# RS485_channel.net
KiCad netlist of a schematic drawn in Altium Designer
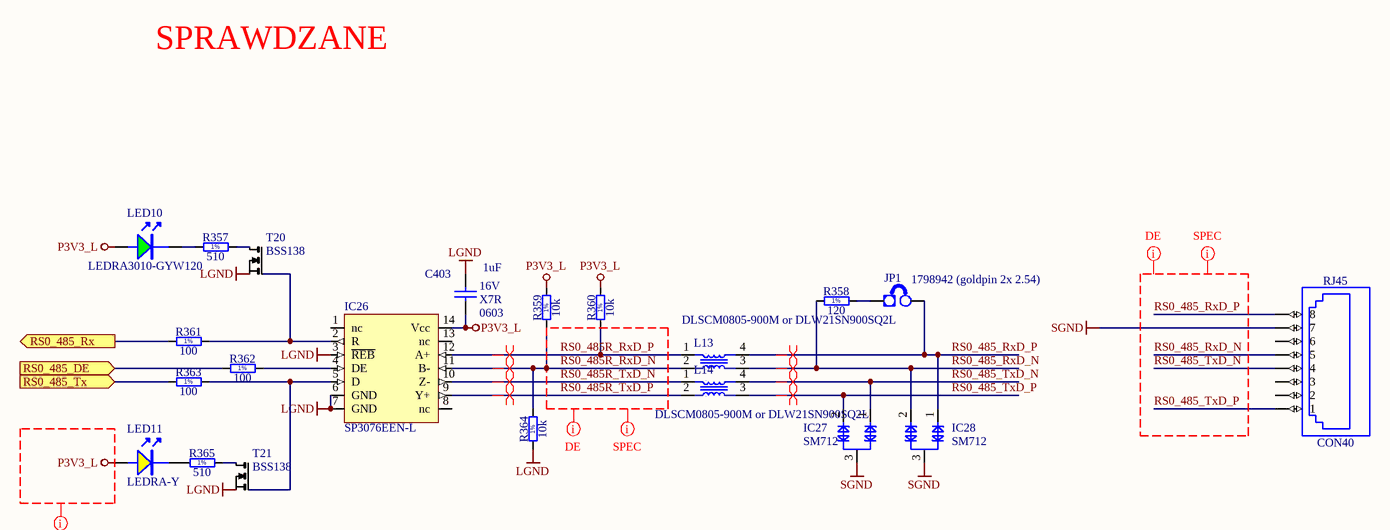
[diagram p0: RS485 channel.SchDoc]

(export (version "E")
  (design (tool "Eeschema 10.0.6"))
  (components
    (comp (ref "C403")
      (value "1uF")
      (footprint "CAPC1608X87N")
      (description "Non-polarised capacitor")
      (fields
        (field (name "PART NUMBER") "CC0603_1UF_16V_10%_X7R")
        (field (name "VOLTAGE") "16V")
        (field (name "TC") "X7R")
        (field (name "TOLERANCE") "±10%")
        (field (name "CASE") "0603")
        (field (name "AUTHOR") "CERN DEM JLC")
      )
      (libsource (lib "Capacitors") (part "Capacitor - non polarized"))
    )
    (comp (ref "CON40")
      (value "RJ45")
      (footprint "FCI_54602-908LF")
      (description "1 Port, 8 Positions, CAT3 RJ45 Horizontal Modular Jack")
      (fields
        (field (name "PART NUMBER") "FCI_54602-908LF")
        (field (name "MANUFACTURER") "FCI")
        (field (name "AUTHOR") "CERN DEM JLC")
      )
      (libsource (lib "Connectors") (part "FCI_54602-908LF"))
    )
    (comp (ref "IC26")
      (value "SP3076EEN-L")
      (footprint "SO-14")
      (description "3.3V, 1/8 Load, Failsafe  RS-485/RS422 Transceivers")
      (libsource (lib "LIBRARY_SCH") (part "DRV_SP3070/73/76"))
    )
    (comp (ref "IC27")
      (value "SM712")
      (footprint "SOT-23")
      (description "Asymmetrical TVS Diode for RS485")
      (libsource (lib "LIBRARY_SCH") (part "D_TVS_SM712"))
    )
    (comp (ref "IC28")
      (value "SM712")
      (footprint "SOT-23")
      (description "Asymmetrical TVS Diode for RS485")
      (libsource (lib "LIBRARY_SCH") (part "D_TVS_SM712"))
    )
    (comp (ref "JP1")
      (value "1798942 (goldpin 2x 2.54)")
      (footprint "jump")
      (description "Jumper")
      (libsource (lib "LIBRARY_SCH") (part "JUMPER"))
    )
    (comp (ref "L13")
      (value "DLSCM0805-900M or DLW21SN900SQ2L")
      (footprint "DLSCM0805")
      (description "Common Mode Choke 90R")
      (libsource (lib "LIBRARY_SCH") (part "L_CMC_DLSCM0805_90R"))
    )
    (comp (ref "L14")
      (value "DLSCM0805-900M or DLW21SN900SQ2L")
      (footprint "DLSCM0805")
      (description "Common Mode Choke 90R")
      (libsource (lib "LIBRARY_SCH") (part "L_CMC_DLSCM0805_90R"))
    )
    (comp (ref "LED10")
      (value "LEDRA3010-GYW120")
      (footprint "LED_KPA3010_G")
      (description "LED (Maritex)")
      (libsource (lib "LIBRARY_SCH") (part "LED_SMD_90deg_G"))
    )
    (comp (ref "LED11")
      (value "LEDRA-Y")
      (footprint "LED_KPA3010_Y")
      (description "LED (maritex)")
      (libsource (lib "LIBRARY_SCH") (part "LED_SMD_90deg_Y"))
    )
    (comp (ref "R357")
      (value "510")
      (footprint "RESC1608X55N")
      (description "Resistor - 1%")
      (fields
        (field (name "PART NUMBER") "R0603_510R_1%_0.1W_100PPM")
        (field (name "POWER") "0.1W")
        (field (name "AUTHOR") "CERN DEM JLC")
      )
      (libsource (lib "Resistors") (part "Resistor - 1%"))
    )
    (comp (ref "R358")
      (value "120")
      (footprint "RESC3216X65N")
      (description "Resistor - 1%")
      (fields
        (field (name "PART NUMBER") "R1206_120R_1%_0.25W_100PPM")
        (field (name "POWER") "0.25W")
        (field (name "AUTHOR") "CERN DEM JLC")
      )
      (libsource (lib "Resistors") (part "Resistor - 1%"))
    )
    (comp (ref "R359")
      (value "10k")
      (footprint "RESC1005X40N")
      (description "Resistor - 1%")
      (fields
        (field (name "PART NUMBER") "R0402_10K_1%_0.0625W_100PPM")
        (field (name "POWER") "0.0625W")
        (field (name "AUTHOR") "CERN DEM JLC")
      )
      (libsource (lib "Resistors") (part "Resistor - 1%"))
    )
    (comp (ref "R360")
      (value "10k")
      (footprint "RESC1005X40N")
      (description "Resistor - 1%")
      (fields
        (field (name "PART NUMBER") "R0402_10K_1%_0.0625W_100PPM")
        (field (name "POWER") "0.0625W")
        (field (name "AUTHOR") "CERN DEM JLC")
      )
      (libsource (lib "Resistors") (part "Resistor - 1%"))
    )
    (comp (ref "R361")
      (value "100")
      (footprint "RESC1005X40N")
      (description "Resistor - 1%")
      (fields
        (field (name "PART NUMBER") "R0402_100R_1%_0.0625W_100PPM")
        (field (name "POWER") "0.0625W")
        (field (name "AUTHOR") "CERN DEM JLC")
      )
      (libsource (lib "Resistors") (part "Resistor - 1%"))
    )
    (comp (ref "R362")
      (value "100")
      (footprint "RESC1005X40N")
      (description "Resistor - 1%")
      (fields
        (field (name "PART NUMBER") "R0402_100R_1%_0.0625W_100PPM")
        (field (name "POWER") "0.0625W")
        (field (name "AUTHOR") "CERN DEM JLC")
      )
      (libsource (lib "Resistors") (part "Resistor - 1%"))
    )
    (comp (ref "R363")
      (value "100")
      (footprint "RESC1005X40N")
      (description "Resistor - 1%")
      (fields
        (field (name "PART NUMBER") "R0402_100R_1%_0.0625W_100PPM")
        (field (name "POWER") "0.0625W")
        (field (name "AUTHOR") "CERN DEM JLC")
      )
      (libsource (lib "Resistors") (part "Resistor - 1%"))
    )
    (comp (ref "R364")
      (value "10k")
      (footprint "RESC1005X40N")
      (description "Resistor - 1%")
      (fields
        (field (name "PART NUMBER") "R0402_10K_1%_0.0625W_100PPM")
        (field (name "POWER") "0.0625W")
        (field (name "AUTHOR") "CERN DEM JLC")
      )
      (libsource (lib "Resistors") (part "Resistor - 1%"))
    )
    (comp (ref "R365")
      (value "510")
      (footprint "RESC1608X55N")
      (description "Resistor - 1%")
      (fields
        (field (name "PART NUMBER") "R0603_510R_1%_0.1W_100PPM")
        (field (name "POWER") "0.1W")
        (field (name "AUTHOR") "CERN DEM JLC")
      )
      (libsource (lib "Resistors") (part "Resistor - 1%"))
    )
    (comp (ref "T20") (value "BSS138") (footprint "SOT-23") (libsource (lib "LIBRARY_SCH") (part "Q_BSS138")))
    (comp (ref "T21") (value "BSS138") (footprint "SOT-23") (libsource (lib "LIBRARY_SCH") (part "Q_BSS138")))
  )
  (nets
    (net (code "1") (name "/RS0_485R_RxD_N") (class "Default")
      (node (ref "IC26") (pin "11") (pinfunction "B-_11") (pintype "input"))
      (node (ref "L13") (pin "2") (pinfunction "2_2") (pintype "passive"))
      (node (ref "R359") (pin "1") (pinfunction "1_1") (pintype "passive"))
      (node (ref "R364") (pin "2") (pinfunction "2_2") (pintype "passive"))
    )
    (net (code "2") (name "/RS0_485R_RxD_P") (class "Default")
      (node (ref "IC26") (pin "12") (pinfunction "A+_12") (pintype "input"))
      (node (ref "L13") (pin "1") (pinfunction "1_1") (pintype "passive"))
      (node (ref "R360") (pin "1") (pinfunction "1_1") (pintype "passive"))
    )
    (net (code "3") (name "/RS0_485R_TxD_N") (class "Default")
      (node (ref "IC26") (pin "10") (pinfunction "Z-_10") (pintype "output"))
      (node (ref "L14") (pin "1") (pinfunction "1_1") (pintype "passive"))
    )
    (net (code "4") (name "/RS0_485R_TxD_P") (class "Default")
      (node (ref "IC26") (pin "9") (pinfunction "Y+_9") (pintype "output"))
      (node (ref "L14") (pin "2") (pinfunction "2_2") (pintype "passive"))
    )
    (net (code "5") (name "/RS0_485_DE") (class "Default")
      (node (ref "R362") (pin "1") (pinfunction "1_1") (pintype "passive"))
    )
    (net (code "6") (name "/RS0_485_Rx") (class "Default")
      (node (ref "R361") (pin "1") (pinfunction "1_1") (pintype "passive"))
    )
    (net (code "7") (name "/RS0_485_RxD_N") (class "Default")
      (node (ref "CON40") (pin "5") (pinfunction "5_5") (pintype "bidirectional"))
      (node (ref "IC28") (pin "2") (pinfunction "2_2") (pintype "passive"))
      (node (ref "L13") (pin "3") (pinfunction "3_3") (pintype "passive"))
      (node (ref "R358") (pin "1") (pinfunction "1_1") (pintype "passive"))
    )
    (net (code "8") (name "/RS0_485_RxD_P") (class "Default")
      (node (ref "CON40") (pin "8") (pinfunction "8_8") (pintype "bidirectional"))
      (node (ref "IC28") (pin "1") (pinfunction "1_1") (pintype "passive"))
      (node (ref "JP1") (pin "2") (pinfunction "E2_2") (pintype "passive"))
      (node (ref "L13") (pin "4") (pinfunction "4_4") (pintype "passive"))
    )
    (net (code "9") (name "/RS0_485_Tx") (class "Default")
      (node (ref "R363") (pin "1") (pinfunction "1_1") (pintype "passive"))
    )
    (net (code "10") (name "/RS0_485_TxD_N") (class "Default")
      (node (ref "CON40") (pin "4") (pinfunction "4_4") (pintype "bidirectional"))
      (node (ref "IC27") (pin "1") (pinfunction "1_1") (pintype "passive"))
      (node (ref "L14") (pin "4") (pinfunction "4_4") (pintype "passive"))
    )
    (net (code "11") (name "/RS0_485_TxD_P") (class "Default")
      (node (ref "CON40") (pin "1") (pinfunction "1_1") (pintype "bidirectional"))
      (node (ref "IC27") (pin "2") (pinfunction "2_2") (pintype "passive"))
      (node (ref "L14") (pin "3") (pinfunction "3_3") (pintype "passive"))
    )
    (net (code "12") (name "LGND") (class "Default")
      (node (ref "C403") (pin "2") (pinfunction "2_2") (pintype "passive"))
      (node (ref "IC26") (pin "3") (pinfunction "~{REB}_3") (pintype "input"))
      (node (ref "IC26") (pin "6") (pinfunction "GND_6") (pintype "power_in"))
      (node (ref "IC26") (pin "7") (pinfunction "GND_7") (pintype "power_in"))
      (node (ref "R364") (pin "1") (pinfunction "1_1") (pintype "passive"))
      (node (ref "T20") (pin "2") (pinfunction "S_2") (pintype "passive"))
      (node (ref "T21") (pin "2") (pinfunction "S_2") (pintype "passive"))
    )
    (net (code "13") (name "Net-(IC26-D)") (class "Default")
      (node (ref "IC26") (pin "5") (pinfunction "D_5") (pintype "input"))
      (node (ref "R363") (pin "2") (pinfunction "2_2") (pintype "passive"))
      (node (ref "T21") (pin "1") (pinfunction "G_1") (pintype "input"))
    )
    (net (code "14") (name "Net-(IC26-DE)") (class "Default")
      (node (ref "IC26") (pin "4") (pinfunction "DE_4") (pintype "input"))
      (node (ref "R362") (pin "2") (pinfunction "2_2") (pintype "passive"))
    )
    (net (code "15") (name "Net-(IC26-R)") (class "Default")
      (node (ref "IC26") (pin "2") (pinfunction "R_2") (pintype "output"))
      (node (ref "R361") (pin "2") (pinfunction "2_2") (pintype "passive"))
      (node (ref "T20") (pin "1") (pinfunction "G_1") (pintype "input"))
    )
    (net (code "16") (name "Net-(JP1-E1)") (class "Default")
      (node (ref "JP1") (pin "1") (pinfunction "E1_1") (pintype "passive"))
      (node (ref "R358") (pin "2") (pinfunction "2_2") (pintype "passive"))
    )
    (net (code "17") (name "Net-(LED10-PadK)") (class "Default")
      (node (ref "LED10") (pin "K") (pinfunction "K_K") (pintype "passive"))
      (node (ref "R357") (pin "1") (pinfunction "1_1") (pintype "passive"))
    )
    (net (code "18") (name "Net-(LED11-PadK)") (class "Default")
      (node (ref "LED11") (pin "K") (pinfunction "K_K") (pintype "passive"))
      (node (ref "R365") (pin "1") (pinfunction "1_1") (pintype "passive"))
    )
    (net (code "19") (name "Net-(T20-D)") (class "Default")
      (node (ref "R357") (pin "2") (pinfunction "2_2") (pintype "passive"))
      (node (ref "T20") (pin "3") (pinfunction "D_3") (pintype "passive"))
    )
    (net (code "20") (name "Net-(T21-D)") (class "Default")
      (node (ref "R365") (pin "2") (pinfunction "2_2") (pintype "passive"))
      (node (ref "T21") (pin "3") (pinfunction "D_3") (pintype "passive"))
    )
    (net (code "21") (name "P3V3_L") (class "Default")
      (node (ref "C403") (pin "1") (pinfunction "1_1") (pintype "passive"))
      (node (ref "IC26") (pin "14") (pinfunction "Vcc_14") (pintype "power_in"))
      (node (ref "LED10") (pin "A") (pinfunction "A_A") (pintype "passive"))
      (node (ref "LED11") (pin "A") (pinfunction "A_A") (pintype "passive"))
      (node (ref "R359") (pin "2") (pinfunction "2_2") (pintype "passive"))
      (node (ref "R360") (pin "2") (pinfunction "2_2") (pintype "passive"))
    )
    (net (code "22") (name "SGND") (class "Default")
      (node (ref "CON40") (pin "7") (pinfunction "7_7") (pintype "bidirectional"))
      (node (ref "IC27") (pin "3") (pinfunction "3_3") (pintype "passive"))
      (node (ref "IC28") (pin "3") (pinfunction "3_3") (pintype "passive"))
    )
    (net (code "23") (name "unconnected-(CON40-Pad2)") (class "Default")
      (node (ref "CON40") (pin "2") (pinfunction "2_2") (pintype "bidirectional"))
    )
    (net (code "24") (name "unconnected-(CON40-Pad3)") (class "Default")
      (node (ref "CON40") (pin "3") (pinfunction "3_3") (pintype "bidirectional"))
    )
    (net (code "25") (name "unconnected-(CON40-Pad6)") (class "Default")
      (node (ref "CON40") (pin "6") (pinfunction "6_6") (pintype "bidirectional"))
    )
    (net (code "26") (name "unconnected-(IC26-nc-Pad1)") (class "Default")
      (node (ref "IC26") (pin "1") (pinfunction "nc_1") (pintype "passive"))
    )
    (net (code "27") (name "unconnected-(IC26-nc-Pad8)") (class "Default")
      (node (ref "IC26") (pin "8") (pinfunction "nc_8") (pintype "passive"))
    )
    (net (code "28") (name "unconnected-(IC26-nc-Pad13)") (class "Default")
      (node (ref "IC26") (pin "13") (pinfunction "nc_13") (pintype "passive"))
    )
  )
)
